# LedPanel.net
KiCad netlist of a schematic drawn in EAGLE
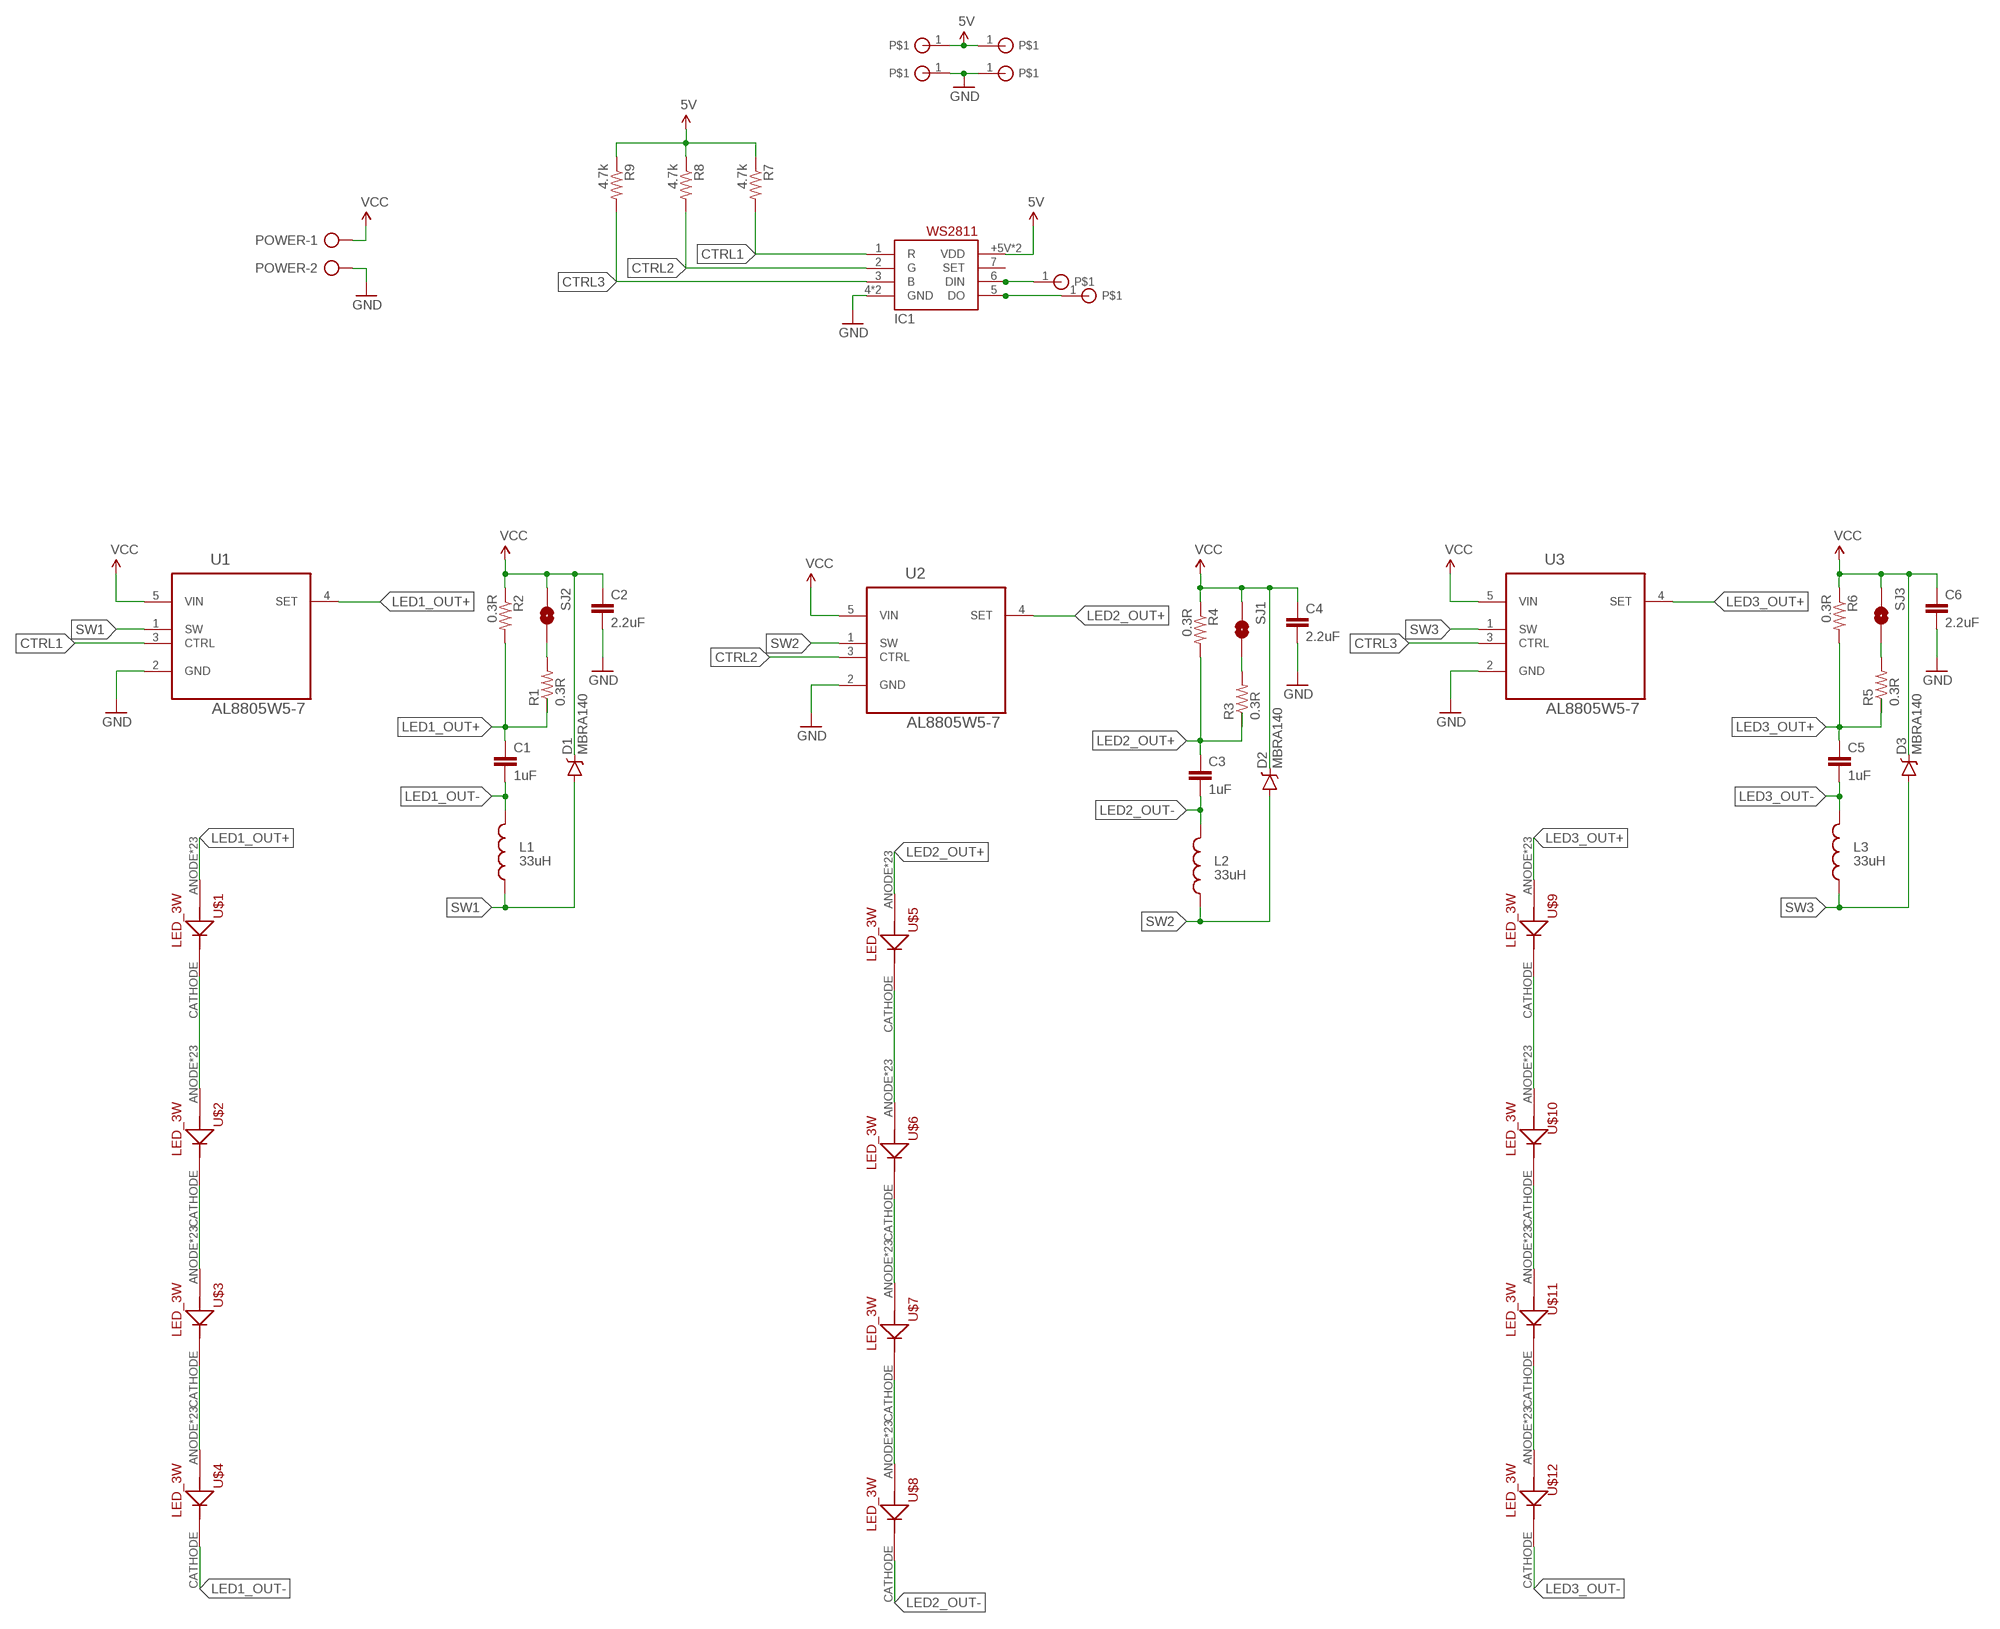
[diagram p0: schematic, sheet 1]

(export (version "E")
  (design (tool "Eeschema 10.0.6"))
  (components
    (comp (ref "5V")
      (value "5V")
      (footprint "eagle-import:SOLDER_PAD")
      (libsource (lib "eagle-import") (part "SOLDER_PAD"))
    )
    (comp (ref "C1")
      (value "1uF")
      (footprint "eagle-import:1206-CAP")
      (libsource (lib "eagle-import") (part "1.0UF50V10%(1206)"))
    )
    (comp (ref "C2")
      (value "2.2uF")
      (footprint "eagle-import:1206-CAP")
      (libsource (lib "eagle-import") (part "2.2UF50V10%(1206)"))
    )
    (comp (ref "C3")
      (value "1uF")
      (footprint "eagle-import:1206-CAP")
      (libsource (lib "eagle-import") (part "1.0UF50V10%(1206)"))
    )
    (comp (ref "C4")
      (value "2.2uF")
      (footprint "eagle-import:1206-CAP")
      (libsource (lib "eagle-import") (part "2.2UF50V10%(1206)"))
    )
    (comp (ref "C5")
      (value "1uF")
      (footprint "eagle-import:1206-CAP")
      (libsource (lib "eagle-import") (part "1.0UF50V10%(1206)"))
    )
    (comp (ref "C6")
      (value "2.2uF")
      (footprint "eagle-import:1206-CAP")
      (libsource (lib "eagle-import") (part "2.2UF50V10%(1206)"))
    )
    (comp (ref "D1")
      (value "MBRA140")
      (footprint "eagle-import:SMA-DIODE")
      (libsource (lib "eagle-import") (part "DIODE-SCHOTTKY-MBRA140"))
    )
    (comp (ref "D2")
      (value "MBRA140")
      (footprint "eagle-import:SMA-DIODE")
      (libsource (lib "eagle-import") (part "DIODE-SCHOTTKY-MBRA140"))
    )
    (comp (ref "D3")
      (value "MBRA140")
      (footprint "eagle-import:SMA-DIODE")
      (libsource (lib "eagle-import") (part "DIODE-SCHOTTKY-MBRA140"))
    )
    (comp (ref "DI")
      (value "DI")
      (footprint "eagle-import:SOLDER_PAD")
      (libsource (lib "eagle-import") (part "SOLDER_PAD"))
    )
    (comp (ref "DO")
      (value "DO")
      (footprint "eagle-import:SOLDER_PAD")
      (libsource (lib "eagle-import") (part "SOLDER_PAD"))
    )
    (comp (ref "IC1")
      (value "WS2811-SOP8")
      (footprint "eagle-import:SO08-SKINNYPADS")
      (libsource (lib "eagle-import") (part "WS2811-SOP8"))
    )
    (comp (ref "L1")
      (value "33uH")
      (footprint "eagle-import:SRN6045")
      (libsource (lib "eagle-import") (part "INDUCTORBOURNS_SRN6045"))
    )
    (comp (ref "L2")
      (value "33uH")
      (footprint "eagle-import:SRN6045")
      (libsource (lib "eagle-import") (part "INDUCTORBOURNS_SRN6045"))
    )
    (comp (ref "L3")
      (value "33uH")
      (footprint "eagle-import:SRN6045")
      (libsource (lib "eagle-import") (part "INDUCTORBOURNS_SRN6045"))
    )
    (comp (ref "POWER")
      (value "AK500/2")
      (footprint "eagle-import:AK500_2")
      (libsource (lib "eagle-import") (part "AK500/2"))
    )
    (comp (ref "R1")
      (value "0.3R")
      (footprint "eagle-import:0805")
      (libsource (lib "eagle-import") (part "0.3OHM-1/8W-1%(0805)"))
    )
    (comp (ref "R2")
      (value "0.3R")
      (footprint "eagle-import:0805")
      (libsource (lib "eagle-import") (part "0.3OHM-1/8W-1%(0805)"))
    )
    (comp (ref "R3")
      (value "0.3R")
      (footprint "eagle-import:0805")
      (libsource (lib "eagle-import") (part "0.3OHM-1/8W-1%(0805)"))
    )
    (comp (ref "R4")
      (value "0.3R")
      (footprint "eagle-import:0805")
      (libsource (lib "eagle-import") (part "0.3OHM-1/8W-1%(0805)"))
    )
    (comp (ref "R5")
      (value "0.3R")
      (footprint "eagle-import:0805")
      (libsource (lib "eagle-import") (part "0.3OHM-1/8W-1%(0805)"))
    )
    (comp (ref "R6")
      (value "0.3R")
      (footprint "eagle-import:0805")
      (libsource (lib "eagle-import") (part "0.3OHM-1/8W-1%(0805)"))
    )
    (comp (ref "R7")
      (value "4.7k")
      (footprint "eagle-import:0805")
      (libsource (lib "eagle-import") (part "0.3OHM-1/8W-1%(0805)"))
    )
    (comp (ref "R8")
      (value "4.7k")
      (footprint "eagle-import:0805")
      (libsource (lib "eagle-import") (part "0.3OHM-1/8W-1%(0805)"))
    )
    (comp (ref "R9")
      (value "4.7k")
      (footprint "eagle-import:0805")
      (libsource (lib "eagle-import") (part "0.3OHM-1/8W-1%(0805)"))
    )
    (comp (ref "SJ1")
      (value "NO Jumper")
      (footprint "eagle-import:PAD-JUMPER-2-NO_NO_SILK")
      (libsource (lib "eagle-import") (part "JUMPER-PAD-2-NO"))
    )
    (comp (ref "SJ2")
      (value "NO Jumper")
      (footprint "eagle-import:PAD-JUMPER-2-NO_NO_SILK")
      (libsource (lib "eagle-import") (part "JUMPER-PAD-2-NO"))
    )
    (comp (ref "SJ3")
      (value "NO Jumper")
      (footprint "eagle-import:PAD-JUMPER-2-NO_NO_SILK")
      (libsource (lib "eagle-import") (part "JUMPER-PAD-2-NO"))
    )
    (comp (ref "U$1")
      (value "LED_3W")
      (footprint "eagle-import:LED_3W")
      (libsource (lib "eagle-import") (part "LED_3W"))
    )
    (comp (ref "U$2")
      (value "LED_3W")
      (footprint "eagle-import:LED_3W")
      (libsource (lib "eagle-import") (part "LED_3W"))
    )
    (comp (ref "U$3")
      (value "LED_3W")
      (footprint "eagle-import:LED_3W")
      (libsource (lib "eagle-import") (part "LED_3W"))
    )
    (comp (ref "U$4")
      (value "LED_3W")
      (footprint "eagle-import:LED_3W")
      (libsource (lib "eagle-import") (part "LED_3W"))
    )
    (comp (ref "U$5")
      (value "LED_3W")
      (footprint "eagle-import:LED_3W")
      (libsource (lib "eagle-import") (part "LED_3W"))
    )
    (comp (ref "U$6")
      (value "LED_3W")
      (footprint "eagle-import:LED_3W")
      (libsource (lib "eagle-import") (part "LED_3W"))
    )
    (comp (ref "U$7")
      (value "LED_3W")
      (footprint "eagle-import:LED_3W")
      (libsource (lib "eagle-import") (part "LED_3W"))
    )
    (comp (ref "U$8")
      (value "LED_3W")
      (footprint "eagle-import:LED_3W")
      (libsource (lib "eagle-import") (part "LED_3W"))
    )
    (comp (ref "U$9")
      (value "LED_3W")
      (footprint "eagle-import:LED_3W")
      (libsource (lib "eagle-import") (part "LED_3W"))
    )
    (comp (ref "U$10")
      (value "LED_3W")
      (footprint "eagle-import:LED_3W")
      (libsource (lib "eagle-import") (part "LED_3W"))
    )
    (comp (ref "U$11")
      (value "LED_3W")
      (footprint "eagle-import:LED_3W")
      (libsource (lib "eagle-import") (part "LED_3W"))
    )
    (comp (ref "U$12")
      (value "LED_3W")
      (footprint "eagle-import:LED_3W")
      (libsource (lib "eagle-import") (part "LED_3W"))
    )
    (comp (ref "U$15")
      (value "GND")
      (footprint "eagle-import:SOLDER_PAD")
      (libsource (lib "eagle-import") (part "SOLDER_PAD"))
    )
    (comp (ref "U$16")
      (value "5V")
      (footprint "eagle-import:SOLDER_PAD")
      (libsource (lib "eagle-import") (part "SOLDER_PAD"))
    )
    (comp (ref "U$18")
      (value "GND")
      (footprint "eagle-import:SOLDER_PAD")
      (libsource (lib "eagle-import") (part "SOLDER_PAD"))
    )
    (comp (ref "U1")
      (value "AL8805W5-7")
      (footprint "eagle-import:SOT95P280X130-5N")
      (libsource (lib "eagle-import") (part "AL8805W5-7"))
    )
    (comp (ref "U2")
      (value "AL8805W5-7")
      (footprint "eagle-import:SOT95P280X130-5N")
      (libsource (lib "eagle-import") (part "AL8805W5-7"))
    )
    (comp (ref "U3")
      (value "AL8805W5-7")
      (footprint "eagle-import:SOT95P280X130-5N")
      (libsource (lib "eagle-import") (part "AL8805W5-7"))
    )
  )
  (nets
    (net (code "1") (name "5V") (class "Default")
      (node (ref "5V") (pin "1") (pinfunction "P$1_1") (pintype "bidirectional"))
      (node (ref "IC1") (pin "+5V") (pinfunction "VDD_+5V") (pintype "power_in"))
      (node (ref "IC1") (pin "8") (pinfunction "VDD_8") (pintype "power_in"))
      (node (ref "R7") (pin "1") (pinfunction "1_1") (pintype "passive"))
      (node (ref "R8") (pin "1") (pinfunction "1_1") (pintype "passive"))
      (node (ref "R9") (pin "1") (pinfunction "1_1") (pintype "passive"))
      (node (ref "U$16") (pin "1") (pinfunction "P$1_1") (pintype "bidirectional"))
    )
    (net (code "2") (name "CTRL1") (class "Default")
      (node (ref "IC1") (pin "1") (pinfunction "R_1") (pintype "open_collector"))
      (node (ref "R7") (pin "2") (pinfunction "2_2") (pintype "passive"))
      (node (ref "U1") (pin "3") (pinfunction "CTRL_3") (pintype "input"))
    )
    (net (code "3") (name "CTRL2") (class "Default")
      (node (ref "IC1") (pin "2") (pinfunction "G_2") (pintype "open_collector"))
      (node (ref "R8") (pin "2") (pinfunction "2_2") (pintype "passive"))
      (node (ref "U2") (pin "3") (pinfunction "CTRL_3") (pintype "input"))
    )
    (net (code "4") (name "CTRL3") (class "Default")
      (node (ref "IC1") (pin "3") (pinfunction "B_3") (pintype "open_collector"))
      (node (ref "R9") (pin "2") (pinfunction "2_2") (pintype "passive"))
      (node (ref "U3") (pin "3") (pinfunction "CTRL_3") (pintype "input"))
    )
    (net (code "5") (name "GND") (class "Default")
      (node (ref "C2") (pin "2") (pinfunction "2_2") (pintype "passive"))
      (node (ref "C4") (pin "2") (pinfunction "2_2") (pintype "passive"))
      (node (ref "C6") (pin "2") (pinfunction "2_2") (pintype "passive"))
      (node (ref "IC1") (pin "4") (pinfunction "GND_4") (pintype "power_in"))
      (node (ref "IC1") (pin "GND") (pinfunction "GND_GND") (pintype "power_in"))
      (node (ref "POWER") (pin "2") (pinfunction "KL_2") (pintype "passive"))
      (node (ref "U$15") (pin "1") (pinfunction "P$1_1") (pintype "bidirectional"))
      (node (ref "U$18") (pin "1") (pinfunction "P$1_1") (pintype "bidirectional"))
      (node (ref "U1") (pin "2") (pinfunction "GND_2") (pintype "passive"))
      (node (ref "U2") (pin "2") (pinfunction "GND_2") (pintype "passive"))
      (node (ref "U3") (pin "2") (pinfunction "GND_2") (pintype "passive"))
    )
    (net (code "6") (name "LED1_OUT+") (class "Default")
      (node (ref "C1") (pin "1") (pinfunction "1_1") (pintype "passive"))
      (node (ref "R1") (pin "1") (pinfunction "1_1") (pintype "passive"))
      (node (ref "R2") (pin "2") (pinfunction "2_2") (pintype "passive"))
      (node (ref "U$1") (pin "ANODE") (pinfunction "ANODE_ANODE") (pintype "bidirectional"))
      (node (ref "U$1") (pin "P$1") (pinfunction "ANODE_P$1") (pintype "bidirectional"))
      (node (ref "U$1") (pin "P$10") (pinfunction "ANODE_P$10") (pintype "bidirectional"))
      (node (ref "U$1") (pin "P$11") (pinfunction "ANODE_P$11") (pintype "bidirectional"))
      (node (ref "U$1") (pin "P$12") (pinfunction "ANODE_P$12") (pintype "bidirectional"))
      (node (ref "U$1") (pin "P$13") (pinfunction "ANODE_P$13") (pintype "bidirectional"))
      (node (ref "U$1") (pin "P$14") (pinfunction "ANODE_P$14") (pintype "bidirectional"))
      (node (ref "U$1") (pin "P$15") (pinfunction "ANODE_P$15") (pintype "bidirectional"))
      (node (ref "U$1") (pin "P$16") (pinfunction "ANODE_P$16") (pintype "bidirectional"))
      (node (ref "U$1") (pin "P$17") (pinfunction "ANODE_P$17") (pintype "bidirectional"))
      (node (ref "U$1") (pin "P$18") (pinfunction "ANODE_P$18") (pintype "bidirectional"))
      (node (ref "U$1") (pin "P$19") (pinfunction "ANODE_P$19") (pintype "bidirectional"))
      (node (ref "U$1") (pin "P$2") (pinfunction "ANODE_P$2") (pintype "bidirectional"))
      (node (ref "U$1") (pin "P$20") (pinfunction "ANODE_P$20") (pintype "bidirectional"))
      (node (ref "U$1") (pin "P$21") (pinfunction "ANODE_P$21") (pintype "bidirectional"))
      (node (ref "U$1") (pin "P$3") (pinfunction "ANODE_P$3") (pintype "bidirectional"))
      (node (ref "U$1") (pin "P$4") (pinfunction "ANODE_P$4") (pintype "bidirectional"))
      (node (ref "U$1") (pin "P$5") (pinfunction "ANODE_P$5") (pintype "bidirectional"))
      (node (ref "U$1") (pin "P$6") (pinfunction "ANODE_P$6") (pintype "bidirectional"))
      (node (ref "U$1") (pin "P$7") (pinfunction "ANODE_P$7") (pintype "bidirectional"))
      (node (ref "U$1") (pin "P$8") (pinfunction "ANODE_P$8") (pintype "bidirectional"))
      (node (ref "U$1") (pin "P$9") (pinfunction "ANODE_P$9") (pintype "bidirectional"))
      (node (ref "U$1") (pin "SLUG") (pinfunction "ANODE_SLUG") (pintype "bidirectional"))
      (node (ref "U1") (pin "4") (pinfunction "SET_4") (pintype "output"))
    )
    (net (code "7") (name "LED1_OUT-") (class "Default")
      (node (ref "C1") (pin "2") (pinfunction "2_2") (pintype "passive"))
      (node (ref "L1") (pin "2") (pinfunction "2_2") (pintype "passive"))
      (node (ref "U$4") (pin "CATHODE") (pinfunction "CATHODE_CATHODE") (pintype "bidirectional"))
    )
    (net (code "8") (name "LED2_OUT+") (class "Default")
      (node (ref "C3") (pin "1") (pinfunction "1_1") (pintype "passive"))
      (node (ref "R3") (pin "1") (pinfunction "1_1") (pintype "passive"))
      (node (ref "R4") (pin "2") (pinfunction "2_2") (pintype "passive"))
      (node (ref "U$5") (pin "ANODE") (pinfunction "ANODE_ANODE") (pintype "bidirectional"))
      (node (ref "U$5") (pin "P$1") (pinfunction "ANODE_P$1") (pintype "bidirectional"))
      (node (ref "U$5") (pin "P$10") (pinfunction "ANODE_P$10") (pintype "bidirectional"))
      (node (ref "U$5") (pin "P$11") (pinfunction "ANODE_P$11") (pintype "bidirectional"))
      (node (ref "U$5") (pin "P$12") (pinfunction "ANODE_P$12") (pintype "bidirectional"))
      (node (ref "U$5") (pin "P$13") (pinfunction "ANODE_P$13") (pintype "bidirectional"))
      (node (ref "U$5") (pin "P$14") (pinfunction "ANODE_P$14") (pintype "bidirectional"))
      (node (ref "U$5") (pin "P$15") (pinfunction "ANODE_P$15") (pintype "bidirectional"))
      (node (ref "U$5") (pin "P$16") (pinfunction "ANODE_P$16") (pintype "bidirectional"))
      (node (ref "U$5") (pin "P$17") (pinfunction "ANODE_P$17") (pintype "bidirectional"))
      (node (ref "U$5") (pin "P$18") (pinfunction "ANODE_P$18") (pintype "bidirectional"))
      (node (ref "U$5") (pin "P$19") (pinfunction "ANODE_P$19") (pintype "bidirectional"))
      (node (ref "U$5") (pin "P$2") (pinfunction "ANODE_P$2") (pintype "bidirectional"))
      (node (ref "U$5") (pin "P$20") (pinfunction "ANODE_P$20") (pintype "bidirectional"))
      (node (ref "U$5") (pin "P$21") (pinfunction "ANODE_P$21") (pintype "bidirectional"))
      (node (ref "U$5") (pin "P$3") (pinfunction "ANODE_P$3") (pintype "bidirectional"))
      (node (ref "U$5") (pin "P$4") (pinfunction "ANODE_P$4") (pintype "bidirectional"))
      (node (ref "U$5") (pin "P$5") (pinfunction "ANODE_P$5") (pintype "bidirectional"))
      (node (ref "U$5") (pin "P$6") (pinfunction "ANODE_P$6") (pintype "bidirectional"))
      (node (ref "U$5") (pin "P$7") (pinfunction "ANODE_P$7") (pintype "bidirectional"))
      (node (ref "U$5") (pin "P$8") (pinfunction "ANODE_P$8") (pintype "bidirectional"))
      (node (ref "U$5") (pin "P$9") (pinfunction "ANODE_P$9") (pintype "bidirectional"))
      (node (ref "U$5") (pin "SLUG") (pinfunction "ANODE_SLUG") (pintype "bidirectional"))
      (node (ref "U2") (pin "4") (pinfunction "SET_4") (pintype "output"))
    )
    (net (code "9") (name "LED2_OUT-") (class "Default")
      (node (ref "C3") (pin "2") (pinfunction "2_2") (pintype "passive"))
      (node (ref "L2") (pin "2") (pinfunction "2_2") (pintype "passive"))
      (node (ref "U$8") (pin "CATHODE") (pinfunction "CATHODE_CATHODE") (pintype "bidirectional"))
    )
    (net (code "10") (name "LED3_OUT+") (class "Default")
      (node (ref "C5") (pin "1") (pinfunction "1_1") (pintype "passive"))
      (node (ref "R5") (pin "1") (pinfunction "1_1") (pintype "passive"))
      (node (ref "R6") (pin "2") (pinfunction "2_2") (pintype "passive"))
      (node (ref "U$9") (pin "ANODE") (pinfunction "ANODE_ANODE") (pintype "bidirectional"))
      (node (ref "U$9") (pin "P$1") (pinfunction "ANODE_P$1") (pintype "bidirectional"))
      (node (ref "U$9") (pin "P$10") (pinfunction "ANODE_P$10") (pintype "bidirectional"))
      (node (ref "U$9") (pin "P$11") (pinfunction "ANODE_P$11") (pintype "bidirectional"))
      (node (ref "U$9") (pin "P$12") (pinfunction "ANODE_P$12") (pintype "bidirectional"))
      (node (ref "U$9") (pin "P$13") (pinfunction "ANODE_P$13") (pintype "bidirectional"))
      (node (ref "U$9") (pin "P$14") (pinfunction "ANODE_P$14") (pintype "bidirectional"))
      (node (ref "U$9") (pin "P$15") (pinfunction "ANODE_P$15") (pintype "bidirectional"))
      (node (ref "U$9") (pin "P$16") (pinfunction "ANODE_P$16") (pintype "bidirectional"))
      (node (ref "U$9") (pin "P$17") (pinfunction "ANODE_P$17") (pintype "bidirectional"))
      (node (ref "U$9") (pin "P$18") (pinfunction "ANODE_P$18") (pintype "bidirectional"))
      (node (ref "U$9") (pin "P$19") (pinfunction "ANODE_P$19") (pintype "bidirectional"))
      (node (ref "U$9") (pin "P$2") (pinfunction "ANODE_P$2") (pintype "bidirectional"))
      (node (ref "U$9") (pin "P$20") (pinfunction "ANODE_P$20") (pintype "bidirectional"))
      (node (ref "U$9") (pin "P$21") (pinfunction "ANODE_P$21") (pintype "bidirectional"))
      (node (ref "U$9") (pin "P$3") (pinfunction "ANODE_P$3") (pintype "bidirectional"))
      (node (ref "U$9") (pin "P$4") (pinfunction "ANODE_P$4") (pintype "bidirectional"))
      (node (ref "U$9") (pin "P$5") (pinfunction "ANODE_P$5") (pintype "bidirectional"))
      (node (ref "U$9") (pin "P$6") (pinfunction "ANODE_P$6") (pintype "bidirectional"))
      (node (ref "U$9") (pin "P$7") (pinfunction "ANODE_P$7") (pintype "bidirectional"))
      (node (ref "U$9") (pin "P$8") (pinfunction "ANODE_P$8") (pintype "bidirectional"))
      (node (ref "U$9") (pin "P$9") (pinfunction "ANODE_P$9") (pintype "bidirectional"))
      (node (ref "U$9") (pin "SLUG") (pinfunction "ANODE_SLUG") (pintype "bidirectional"))
      (node (ref "U3") (pin "4") (pinfunction "SET_4") (pintype "output"))
    )
    (net (code "11") (name "LED3_OUT-") (class "Default")
      (node (ref "C5") (pin "2") (pinfunction "2_2") (pintype "passive"))
      (node (ref "L3") (pin "2") (pinfunction "2_2") (pintype "passive"))
      (node (ref "U$12") (pin "CATHODE") (pinfunction "CATHODE_CATHODE") (pintype "bidirectional"))
    )
    (net (code "12") (name "Net-(DI-P$1)") (class "Default")
      (node (ref "DI") (pin "1") (pinfunction "P$1_1") (pintype "bidirectional"))
      (node (ref "IC1") (pin "6") (pinfunction "DIN_6") (pintype "input"))
    )
    (net (code "13") (name "Net-(DO-P$1)") (class "Default")
      (node (ref "DO") (pin "1") (pinfunction "P$1_1") (pintype "bidirectional"))
      (node (ref "IC1") (pin "5") (pinfunction "DO_5") (pintype "output"))
    )
    (net (code "14") (name "Net-(R1-Pad2)") (class "Default")
      (node (ref "R1") (pin "2") (pinfunction "2_2") (pintype "passive"))
      (node (ref "SJ2") (pin "2") (pinfunction "2_2") (pintype "passive"))
    )
    (net (code "15") (name "Net-(R3-Pad2)") (class "Default")
      (node (ref "R3") (pin "2") (pinfunction "2_2") (pintype "passive"))
      (node (ref "SJ1") (pin "2") (pinfunction "2_2") (pintype "passive"))
    )
    (net (code "16") (name "Net-(R5-Pad2)") (class "Default")
      (node (ref "R5") (pin "2") (pinfunction "2_2") (pintype "passive"))
      (node (ref "SJ3") (pin "2") (pinfunction "2_2") (pintype "passive"))
    )
    (net (code "17") (name "Net-(U$1-PadCATHODE)") (class "Default")
      (node (ref "U$1") (pin "CATHODE") (pinfunction "CATHODE_CATHODE") (pintype "bidirectional"))
      (node (ref "U$2") (pin "ANODE") (pinfunction "ANODE_ANODE") (pintype "bidirectional"))
      (node (ref "U$2") (pin "P$1") (pinfunction "ANODE_P$1") (pintype "bidirectional"))
      (node (ref "U$2") (pin "P$10") (pinfunction "ANODE_P$10") (pintype "bidirectional"))
      (node (ref "U$2") (pin "P$11") (pinfunction "ANODE_P$11") (pintype "bidirectional"))
      (node (ref "U$2") (pin "P$12") (pinfunction "ANODE_P$12") (pintype "bidirectional"))
      (node (ref "U$2") (pin "P$13") (pinfunction "ANODE_P$13") (pintype "bidirectional"))
      (node (ref "U$2") (pin "P$14") (pinfunction "ANODE_P$14") (pintype "bidirectional"))
      (node (ref "U$2") (pin "P$15") (pinfunction "ANODE_P$15") (pintype "bidirectional"))
      (node (ref "U$2") (pin "P$16") (pinfunction "ANODE_P$16") (pintype "bidirectional"))
      (node (ref "U$2") (pin "P$17") (pinfunction "ANODE_P$17") (pintype "bidirectional"))
      (node (ref "U$2") (pin "P$18") (pinfunction "ANODE_P$18") (pintype "bidirectional"))
      (node (ref "U$2") (pin "P$19") (pinfunction "ANODE_P$19") (pintype "bidirectional"))
      (node (ref "U$2") (pin "P$2") (pinfunction "ANODE_P$2") (pintype "bidirectional"))
      (node (ref "U$2") (pin "P$20") (pinfunction "ANODE_P$20") (pintype "bidirectional"))
      (node (ref "U$2") (pin "P$21") (pinfunction "ANODE_P$21") (pintype "bidirectional"))
      (node (ref "U$2") (pin "P$3") (pinfunction "ANODE_P$3") (pintype "bidirectional"))
      (node (ref "U$2") (pin "P$4") (pinfunction "ANODE_P$4") (pintype "bidirectional"))
      (node (ref "U$2") (pin "P$5") (pinfunction "ANODE_P$5") (pintype "bidirectional"))
      (node (ref "U$2") (pin "P$6") (pinfunction "ANODE_P$6") (pintype "bidirectional"))
      (node (ref "U$2") (pin "P$7") (pinfunction "ANODE_P$7") (pintype "bidirectional"))
      (node (ref "U$2") (pin "P$8") (pinfunction "ANODE_P$8") (pintype "bidirectional"))
      (node (ref "U$2") (pin "P$9") (pinfunction "ANODE_P$9") (pintype "bidirectional"))
      (node (ref "U$2") (pin "SLUG") (pinfunction "ANODE_SLUG") (pintype "bidirectional"))
    )
    (net (code "18") (name "Net-(U$2-PadCATHODE)") (class "Default")
      (node (ref "U$2") (pin "CATHODE") (pinfunction "CATHODE_CATHODE") (pintype "bidirectional"))
      (node (ref "U$3") (pin "ANODE") (pinfunction "ANODE_ANODE") (pintype "bidirectional"))
      (node (ref "U$3") (pin "P$1") (pinfunction "ANODE_P$1") (pintype "bidirectional"))
      (node (ref "U$3") (pin "P$10") (pinfunction "ANODE_P$10") (pintype "bidirectional"))
      (node (ref "U$3") (pin "P$11") (pinfunction "ANODE_P$11") (pintype "bidirectional"))
      (node (ref "U$3") (pin "P$12") (pinfunction "ANODE_P$12") (pintype "bidirectional"))
      (node (ref "U$3") (pin "P$13") (pinfunction "ANODE_P$13") (pintype "bidirectional"))
      (node (ref "U$3") (pin "P$14") (pinfunction "ANODE_P$14") (pintype "bidirectional"))
      (node (ref "U$3") (pin "P$15") (pinfunction "ANODE_P$15") (pintype "bidirectional"))
      (node (ref "U$3") (pin "P$16") (pinfunction "ANODE_P$16") (pintype "bidirectional"))
      (node (ref "U$3") (pin "P$17") (pinfunction "ANODE_P$17") (pintype "bidirectional"))
      (node (ref "U$3") (pin "P$18") (pinfunction "ANODE_P$18") (pintype "bidirectional"))
      (node (ref "U$3") (pin "P$19") (pinfunction "ANODE_P$19") (pintype "bidirectional"))
      (node (ref "U$3") (pin "P$2") (pinfunction "ANODE_P$2") (pintype "bidirectional"))
      (node (ref "U$3") (pin "P$20") (pinfunction "ANODE_P$20") (pintype "bidirectional"))
      (node (ref "U$3") (pin "P$21") (pinfunction "ANODE_P$21") (pintype "bidirectional"))
      (node (ref "U$3") (pin "P$3") (pinfunction "ANODE_P$3") (pintype "bidirectional"))
      (node (ref "U$3") (pin "P$4") (pinfunction "ANODE_P$4") (pintype "bidirectional"))
      (node (ref "U$3") (pin "P$5") (pinfunction "ANODE_P$5") (pintype "bidirectional"))
      (node (ref "U$3") (pin "P$6") (pinfunction "ANODE_P$6") (pintype "bidirectional"))
      (node (ref "U$3") (pin "P$7") (pinfunction "ANODE_P$7") (pintype "bidirectional"))
      (node (ref "U$3") (pin "P$8") (pinfunction "ANODE_P$8") (pintype "bidirectional"))
      (node (ref "U$3") (pin "P$9") (pinfunction "ANODE_P$9") (pintype "bidirectional"))
      (node (ref "U$3") (pin "SLUG") (pinfunction "ANODE_SLUG") (pintype "bidirectional"))
    )
    (net (code "19") (name "Net-(U$3-PadCATHODE)") (class "Default")
      (node (ref "U$3") (pin "CATHODE") (pinfunction "CATHODE_CATHODE") (pintype "bidirectional"))
      (node (ref "U$4") (pin "ANODE") (pinfunction "ANODE_ANODE") (pintype "bidirectional"))
      (node (ref "U$4") (pin "P$1") (pinfunction "ANODE_P$1") (pintype "bidirectional"))
      (node (ref "U$4") (pin "P$10") (pinfunction "ANODE_P$10") (pintype "bidirectional"))
      (node (ref "U$4") (pin "P$11") (pinfunction "ANODE_P$11") (pintype "bidirectional"))
      (node (ref "U$4") (pin "P$12") (pinfunction "ANODE_P$12") (pintype "bidirectional"))
      (node (ref "U$4") (pin "P$13") (pinfunction "ANODE_P$13") (pintype "bidirectional"))
      (node (ref "U$4") (pin "P$14") (pinfunction "ANODE_P$14") (pintype "bidirectional"))
      (node (ref "U$4") (pin "P$15") (pinfunction "ANODE_P$15") (pintype "bidirectional"))
      (node (ref "U$4") (pin "P$16") (pinfunction "ANODE_P$16") (pintype "bidirectional"))
      (node (ref "U$4") (pin "P$17") (pinfunction "ANODE_P$17") (pintype "bidirectional"))
      (node (ref "U$4") (pin "P$18") (pinfunction "ANODE_P$18") (pintype "bidirectional"))
      (node (ref "U$4") (pin "P$19") (pinfunction "ANODE_P$19") (pintype "bidirectional"))
      (node (ref "U$4") (pin "P$2") (pinfunction "ANODE_P$2") (pintype "bidirectional"))
      (node (ref "U$4") (pin "P$20") (pinfunction "ANODE_P$20") (pintype "bidirectional"))
      (node (ref "U$4") (pin "P$21") (pinfunction "ANODE_P$21") (pintype "bidirectional"))
      (node (ref "U$4") (pin "P$3") (pinfunction "ANODE_P$3") (pintype "bidirectional"))
      (node (ref "U$4") (pin "P$4") (pinfunction "ANODE_P$4") (pintype "bidirectional"))
      (node (ref "U$4") (pin "P$5") (pinfunction "ANODE_P$5") (pintype "bidirectional"))
      (node (ref "U$4") (pin "P$6") (pinfunction "ANODE_P$6") (pintype "bidirectional"))
      (node (ref "U$4") (pin "P$7") (pinfunction "ANODE_P$7") (pintype "bidirectional"))
      (node (ref "U$4") (pin "P$8") (pinfunction "ANODE_P$8") (pintype "bidirectional"))
      (node (ref "U$4") (pin "P$9") (pinfunction "ANODE_P$9") (pintype "bidirectional"))
      (node (ref "U$4") (pin "SLUG") (pinfunction "ANODE_SLUG") (pintype "bidirectional"))
    )
    (net (code "20") (name "Net-(U$5-PadCATHODE)") (class "Default")
      (node (ref "U$5") (pin "CATHODE") (pinfunction "CATHODE_CATHODE") (pintype "bidirectional"))
      (node (ref "U$6") (pin "ANODE") (pinfunction "ANODE_ANODE") (pintype "bidirectional"))
      (node (ref "U$6") (pin "P$1") (pinfunction "ANODE_P$1") (pintype "bidirectional"))
      (node (ref "U$6") (pin "P$10") (pinfunction "ANODE_P$10") (pintype "bidirectional"))
      (node (ref "U$6") (pin "P$11") (pinfunction "ANODE_P$11") (pintype "bidirectional"))
      (node (ref "U$6") (pin "P$12") (pinfunction "ANODE_P$12") (pintype "bidirectional"))
      (node (ref "U$6") (pin "P$13") (pinfunction "ANODE_P$13") (pintype "bidirectional"))
      (node (ref "U$6") (pin "P$14") (pinfunction "ANODE_P$14") (pintype "bidirectional"))
      (node (ref "U$6") (pin "P$15") (pinfunction "ANODE_P$15") (pintype "bidirectional"))
      (node (ref "U$6") (pin "P$16") (pinfunction "ANODE_P$16") (pintype "bidirectional"))
      (node (ref "U$6") (pin "P$17") (pinfunction "ANODE_P$17") (pintype "bidirectional"))
      (node (ref "U$6") (pin "P$18") (pinfunction "ANODE_P$18") (pintype "bidirectional"))
      (node (ref "U$6") (pin "P$19") (pinfunction "ANODE_P$19") (pintype "bidirectional"))
      (node (ref "U$6") (pin "P$2") (pinfunction "ANODE_P$2") (pintype "bidirectional"))
      (node (ref "U$6") (pin "P$20") (pinfunction "ANODE_P$20") (pintype "bidirectional"))
      (node (ref "U$6") (pin "P$21") (pinfunction "ANODE_P$21") (pintype "bidirectional"))
      (node (ref "U$6") (pin "P$3") (pinfunction "ANODE_P$3") (pintype "bidirectional"))
      (node (ref "U$6") (pin "P$4") (pinfunction "ANODE_P$4") (pintype "bidirectional"))
      (node (ref "U$6") (pin "P$5") (pinfunction "ANODE_P$5") (pintype "bidirectional"))
      (node (ref "U$6") (pin "P$6") (pinfunction "ANODE_P$6") (pintype "bidirectional"))
      (node (ref "U$6") (pin "P$7") (pinfunction "ANODE_P$7") (pintype "bidirectional"))
      (node (ref "U$6") (pin "P$8") (pinfunction "ANODE_P$8") (pintype "bidirectional"))
      (node (ref "U$6") (pin "P$9") (pinfunction "ANODE_P$9") (pintype "bidirectional"))
      (node (ref "U$6") (pin "SLUG") (pinfunction "ANODE_SLUG") (pintype "bidirectional"))
    )
    (net (code "21") (name "Net-(U$6-PadCATHODE)") (class "Default")
      (node (ref "U$6") (pin "CATHODE") (pinfunction "CATHODE_CATHODE") (pintype "bidirectional"))
      (node (ref "U$7") (pin "ANODE") (pinfunction "ANODE_ANODE") (pintype "bidirectional"))
      (node (ref "U$7") (pin "P$1") (pinfunction "ANODE_P$1") (pintype "bidirectional"))
      (node (ref "U$7") (pin "P$10") (pinfunction "ANODE_P$10") (pintype "bidirectional"))
      (node (ref "U$7") (pin "P$11") (pinfunction "ANODE_P$11") (pintype "bidirectional"))
      (node (ref "U$7") (pin "P$12") (pinfunction "ANODE_P$12") (pintype "bidirectional"))
      (node (ref "U$7") (pin "P$13") (pinfunction "ANODE_P$13") (pintype "bidirectional"))
      (node (ref "U$7") (pin "P$14") (pinfunction "ANODE_P$14") (pintype "bidirectional"))
      (node (ref "U$7") (pin "P$15") (pinfunction "ANODE_P$15") (pintype "bidirectional"))
      (node (ref "U$7") (pin "P$16") (pinfunction "ANODE_P$16") (pintype "bidirectional"))
      (node (ref "U$7") (pin "P$17") (pinfunction "ANODE_P$17") (pintype "bidirectional"))
      (node (ref "U$7") (pin "P$18") (pinfunction "ANODE_P$18") (pintype "bidirectional"))
      (node (ref "U$7") (pin "P$19") (pinfunction "ANODE_P$19") (pintype "bidirectional"))
      (node (ref "U$7") (pin "P$2") (pinfunction "ANODE_P$2") (pintype "bidirectional"))
      (node (ref "U$7") (pin "P$20") (pinfunction "ANODE_P$20") (pintype "bidirectional"))
      (node (ref "U$7") (pin "P$21") (pinfunction "ANODE_P$21") (pintype "bidirectional"))
      (node (ref "U$7") (pin "P$3") (pinfunction "ANODE_P$3") (pintype "bidirectional"))
      (node (ref "U$7") (pin "P$4") (pinfunction "ANODE_P$4") (pintype "bidirectional"))
      (node (ref "U$7") (pin "P$5") (pinfunction "ANODE_P$5") (pintype "bidirectional"))
      (node (ref "U$7") (pin "P$6") (pinfunction "ANODE_P$6") (pintype "bidirectional"))
      (node (ref "U$7") (pin "P$7") (pinfunction "ANODE_P$7") (pintype "bidirectional"))
      (node (ref "U$7") (pin "P$8") (pinfunction "ANODE_P$8") (pintype "bidirectional"))
      (node (ref "U$7") (pin "P$9") (pinfunction "ANODE_P$9") (pintype "bidirectional"))
      (node (ref "U$7") (pin "SLUG") (pinfunction "ANODE_SLUG") (pintype "bidirectional"))
    )
    (net (code "22") (name "Net-(U$7-PadCATHODE)") (class "Default")
      (node (ref "U$7") (pin "CATHODE") (pinfunction "CATHODE_CATHODE") (pintype "bidirectional"))
      (node (ref "U$8") (pin "ANODE") (pinfunction "ANODE_ANODE") (pintype "bidirectional"))
      (node (ref "U$8") (pin "P$1") (pinfunction "ANODE_P$1") (pintype "bidirectional"))
      (node (ref "U$8") (pin "P$10") (pinfunction "ANODE_P$10") (pintype "bidirectional"))
      (node (ref "U$8") (pin "P$11") (pinfunction "ANODE_P$11") (pintype "bidirectional"))
      (node (ref "U$8") (pin "P$12") (pinfunction "ANODE_P$12") (pintype "bidirectional"))
      (node (ref "U$8") (pin "P$13") (pinfunction "ANODE_P$13") (pintype "bidirectional"))
      (node (ref "U$8") (pin "P$14") (pinfunction "ANODE_P$14") (pintype "bidirectional"))
      (node (ref "U$8") (pin "P$15") (pinfunction "ANODE_P$15") (pintype "bidirectional"))
      (node (ref "U$8") (pin "P$16") (pinfunction "ANODE_P$16") (pintype "bidirectional"))
      (node (ref "U$8") (pin "P$17") (pinfunction "ANODE_P$17") (pintype "bidirectional"))
      (node (ref "U$8") (pin "P$18") (pinfunction "ANODE_P$18") (pintype "bidirectional"))
      (node (ref "U$8") (pin "P$19") (pinfunction "ANODE_P$19") (pintype "bidirectional"))
      (node (ref "U$8") (pin "P$2") (pinfunction "ANODE_P$2") (pintype "bidirectional"))
      (node (ref "U$8") (pin "P$20") (pinfunction "ANODE_P$20") (pintype "bidirectional"))
      (node (ref "U$8") (pin "P$21") (pinfunction "ANODE_P$21") (pintype "bidirectional"))
      (node (ref "U$8") (pin "P$3") (pinfunction "ANODE_P$3") (pintype "bidirectional"))
      (node (ref "U$8") (pin "P$4") (pinfunction "ANODE_P$4") (pintype "bidirectional"))
      (node (ref "U$8") (pin "P$5") (pinfunction "ANODE_P$5") (pintype "bidirectional"))
      (node (ref "U$8") (pin "P$6") (pinfunction "ANODE_P$6") (pintype "bidirectional"))
      (node (ref "U$8") (pin "P$7") (pinfunction "ANODE_P$7") (pintype "bidirectional"))
      (node (ref "U$8") (pin "P$8") (pinfunction "ANODE_P$8") (pintype "bidirectional"))
      (node (ref "U$8") (pin "P$9") (pinfunction "ANODE_P$9") (pintype "bidirectional"))
      (node (ref "U$8") (pin "SLUG") (pinfunction "ANODE_SLUG") (pintype "bidirectional"))
    )
    (net (code "23") (name "Net-(U$10-ANODE-PadP$1)") (class "Default")
      (node (ref "U$10") (pin "ANODE") (pinfunction "ANODE_ANODE") (pintype "bidirectional"))
      (node (ref "U$10") (pin "P$1") (pinfunction "ANODE_P$1") (pintype "bidirectional"))
      (node (ref "U$10") (pin "P$10") (pinfunction "ANODE_P$10") (pintype "bidirectional"))
      (node (ref "U$10") (pin "P$11") (pinfunction "ANODE_P$11") (pintype "bidirectional"))
      (node (ref "U$10") (pin "P$12") (pinfunction "ANODE_P$12") (pintype "bidirectional"))
      (node (ref "U$10") (pin "P$13") (pinfunction "ANODE_P$13") (pintype "bidirectional"))
      (node (ref "U$10") (pin "P$14") (pinfunction "ANODE_P$14") (pintype "bidirectional"))
      (node (ref "U$10") (pin "P$15") (pinfunction "ANODE_P$15") (pintype "bidirectional"))
      (node (ref "U$10") (pin "P$16") (pinfunction "ANODE_P$16") (pintype "bidirectional"))
      (node (ref "U$10") (pin "P$17") (pinfunction "ANODE_P$17") (pintype "bidirectional"))
      (node (ref "U$10") (pin "P$18") (pinfunction "ANODE_P$18") (pintype "bidirectional"))
      (node (ref "U$10") (pin "P$19") (pinfunction "ANODE_P$19") (pintype "bidirectional"))
      (node (ref "U$10") (pin "P$2") (pinfunction "ANODE_P$2") (pintype "bidirectional"))
      (node (ref "U$10") (pin "P$20") (pinfunction "ANODE_P$20") (pintype "bidirectional"))
      (node (ref "U$10") (pin "P$21") (pinfunction "ANODE_P$21") (pintype "bidirectional"))
      (node (ref "U$10") (pin "P$3") (pinfunction "ANODE_P$3") (pintype "bidirectional"))
      (node (ref "U$10") (pin "P$4") (pinfunction "ANODE_P$4") (pintype "bidirectional"))
      (node (ref "U$10") (pin "P$5") (pinfunction "ANODE_P$5") (pintype "bidirectional"))
      (node (ref "U$10") (pin "P$6") (pinfunction "ANODE_P$6") (pintype "bidirectional"))
      (node (ref "U$10") (pin "P$7") (pinfunction "ANODE_P$7") (pintype "bidirectional"))
      (node (ref "U$10") (pin "P$8") (pinfunction "ANODE_P$8") (pintype "bidirectional"))
      (node (ref "U$10") (pin "P$9") (pinfunction "ANODE_P$9") (pintype "bidirectional"))
      (node (ref "U$10") (pin "SLUG") (pinfunction "ANODE_SLUG") (pintype "bidirectional"))
      (node (ref "U$9") (pin "CATHODE") (pinfunction "CATHODE_CATHODE") (pintype "bidirectional"))
    )
    (net (code "24") (name "Net-(U$10-PadCATHODE)") (class "Default")
      (node (ref "U$10") (pin "CATHODE") (pinfunction "CATHODE_CATHODE") (pintype "bidirectional"))
      (node (ref "U$11") (pin "ANODE") (pinfunction "ANODE_ANODE") (pintype "bidirectional"))
      (node (ref "U$11") (pin "P$1") (pinfunction "ANODE_P$1") (pintype "bidirectional"))
      (node (ref "U$11") (pin "P$10") (pinfunction "ANODE_P$10") (pintype "bidirectional"))
      (node (ref "U$11") (pin "P$11") (pinfunction "ANODE_P$11") (pintype "bidirectional"))
      (node (ref "U$11") (pin "P$12") (pinfunction "ANODE_P$12") (pintype "bidirectional"))
      (node (ref "U$11") (pin "P$13") (pinfunction "ANODE_P$13") (pintype "bidirectional"))
      (node (ref "U$11") (pin "P$14") (pinfunction "ANODE_P$14") (pintype "bidirectional"))
      (node (ref "U$11") (pin "P$15") (pinfunction "ANODE_P$15") (pintype "bidirectional"))
      (node (ref "U$11") (pin "P$16") (pinfunction "ANODE_P$16") (pintype "bidirectional"))
      (node (ref "U$11") (pin "P$17") (pinfunction "ANODE_P$17") (pintype "bidirectional"))
      (node (ref "U$11") (pin "P$18") (pinfunction "ANODE_P$18") (pintype "bidirectional"))
      (node (ref "U$11") (pin "P$19") (pinfunction "ANODE_P$19") (pintype "bidirectional"))
      (node (ref "U$11") (pin "P$2") (pinfunction "ANODE_P$2") (pintype "bidirectional"))
      (node (ref "U$11") (pin "P$20") (pinfunction "ANODE_P$20") (pintype "bidirectional"))
      (node (ref "U$11") (pin "P$21") (pinfunction "ANODE_P$21") (pintype "bidirectional"))
      (node (ref "U$11") (pin "P$3") (pinfunction "ANODE_P$3") (pintype "bidirectional"))
      (node (ref "U$11") (pin "P$4") (pinfunction "ANODE_P$4") (pintype "bidirectional"))
      (node (ref "U$11") (pin "P$5") (pinfunction "ANODE_P$5") (pintype "bidirectional"))
      (node (ref "U$11") (pin "P$6") (pinfunction "ANODE_P$6") (pintype "bidirectional"))
      (node (ref "U$11") (pin "P$7") (pinfunction "ANODE_P$7") (pintype "bidirectional"))
      (node (ref "U$11") (pin "P$8") (pinfunction "ANODE_P$8") (pintype "bidirectional"))
      (node (ref "U$11") (pin "P$9") (pinfunction "ANODE_P$9") (pintype "bidirectional"))
      (node (ref "U$11") (pin "SLUG") (pinfunction "ANODE_SLUG") (pintype "bidirectional"))
    )
    (net (code "25") (name "Net-(U$11-PadCATHODE)") (class "Default")
      (node (ref "U$11") (pin "CATHODE") (pinfunction "CATHODE_CATHODE") (pintype "bidirectional"))
      (node (ref "U$12") (pin "ANODE") (pinfunction "ANODE_ANODE") (pintype "bidirectional"))
      (node (ref "U$12") (pin "P$1") (pinfunction "ANODE_P$1") (pintype "bidirectional"))
      (node (ref "U$12") (pin "P$10") (pinfunction "ANODE_P$10") (pintype "bidirectional"))
      (node (ref "U$12") (pin "P$11") (pinfunction "ANODE_P$11") (pintype "bidirectional"))
      (node (ref "U$12") (pin "P$12") (pinfunction "ANODE_P$12") (pintype "bidirectional"))
      (node (ref "U$12") (pin "P$13") (pinfunction "ANODE_P$13") (pintype "bidirectional"))
      (node (ref "U$12") (pin "P$14") (pinfunction "ANODE_P$14") (pintype "bidirectional"))
      (node (ref "U$12") (pin "P$15") (pinfunction "ANODE_P$15") (pintype "bidirectional"))
      (node (ref "U$12") (pin "P$16") (pinfunction "ANODE_P$16") (pintype "bidirectional"))
      (node (ref "U$12") (pin "P$17") (pinfunction "ANODE_P$17") (pintype "bidirectional"))
      (node (ref "U$12") (pin "P$18") (pinfunction "ANODE_P$18") (pintype "bidirectional"))
      (node (ref "U$12") (pin "P$19") (pinfunction "ANODE_P$19") (pintype "bidirectional"))
      (node (ref "U$12") (pin "P$2") (pinfunction "ANODE_P$2") (pintype "bidirectional"))
      (node (ref "U$12") (pin "P$20") (pinfunction "ANODE_P$20") (pintype "bidirectional"))
      (node (ref "U$12") (pin "P$21") (pinfunction "ANODE_P$21") (pintype "bidirectional"))
      (node (ref "U$12") (pin "P$3") (pinfunction "ANODE_P$3") (pintype "bidirectional"))
      (node (ref "U$12") (pin "P$4") (pinfunction "ANODE_P$4") (pintype "bidirectional"))
      (node (ref "U$12") (pin "P$5") (pinfunction "ANODE_P$5") (pintype "bidirectional"))
      (node (ref "U$12") (pin "P$6") (pinfunction "ANODE_P$6") (pintype "bidirectional"))
      (node (ref "U$12") (pin "P$7") (pinfunction "ANODE_P$7") (pintype "bidirectional"))
      (node (ref "U$12") (pin "P$8") (pinfunction "ANODE_P$8") (pintype "bidirectional"))
      (node (ref "U$12") (pin "P$9") (pinfunction "ANODE_P$9") (pintype "bidirectional"))
      (node (ref "U$12") (pin "SLUG") (pinfunction "ANODE_SLUG") (pintype "bidirectional"))
    )
    (net (code "26") (name "SW1") (class "Default")
      (node (ref "D1") (pin "A") (pinfunction "A_A") (pintype "passive"))
      (node (ref "L1") (pin "1") (pinfunction "1_1") (pintype "passive"))
      (node (ref "U1") (pin "1") (pinfunction "SW_1") (pintype "passive"))
    )
    (net (code "27") (name "SW2") (class "Default")
      (node (ref "D2") (pin "A") (pinfunction "A_A") (pintype "passive"))
      (node (ref "L2") (pin "1") (pinfunction "1_1") (pintype "passive"))
      (node (ref "U2") (pin "1") (pinfunction "SW_1") (pintype "passive"))
    )
    (net (code "28") (name "SW3") (class "Default")
      (node (ref "D3") (pin "A") (pinfunction "A_A") (pintype "passive"))
      (node (ref "L3") (pin "1") (pinfunction "1_1") (pintype "passive"))
      (node (ref "U3") (pin "1") (pinfunction "SW_1") (pintype "passive"))
    )
    (net (code "29") (name "VCC") (class "Default")
      (node (ref "C2") (pin "1") (pinfunction "1_1") (pintype "passive"))
      (node (ref "C4") (pin "1") (pinfunction "1_1") (pintype "passive"))
      (node (ref "C6") (pin "1") (pinfunction "1_1") (pintype "passive"))
      (node (ref "D1") (pin "C") (pinfunction "C_C") (pintype "passive"))
      (node (ref "D2") (pin "C") (pinfunction "C_C") (pintype "passive"))
      (node (ref "D3") (pin "C") (pinfunction "C_C") (pintype "passive"))
      (node (ref "POWER") (pin "1") (pinfunction "KL_1") (pintype "passive"))
      (node (ref "R2") (pin "1") (pinfunction "1_1") (pintype "passive"))
      (node (ref "R4") (pin "1") (pinfunction "1_1") (pintype "passive"))
      (node (ref "R6") (pin "1") (pinfunction "1_1") (pintype "passive"))
      (node (ref "SJ1") (pin "1") (pinfunction "1_1") (pintype "passive"))
      (node (ref "SJ2") (pin "1") (pinfunction "1_1") (pintype "passive"))
      (node (ref "SJ3") (pin "1") (pinfunction "1_1") (pintype "passive"))
      (node (ref "U1") (pin "5") (pinfunction "VIN_5") (pintype "power_in"))
      (node (ref "U2") (pin "5") (pinfunction "VIN_5") (pintype "power_in"))
      (node (ref "U3") (pin "5") (pinfunction "VIN_5") (pintype "power_in"))
    )
    (net (code "30") (name "unconnected-(IC1-SET-Pad7)") (class "Default")
      (node (ref "IC1") (pin "7") (pinfunction "SET_7") (pintype "input"))
    )
  )
)
